# Motor.net
KiCad netlist of a schematic drawn in Altium Designer
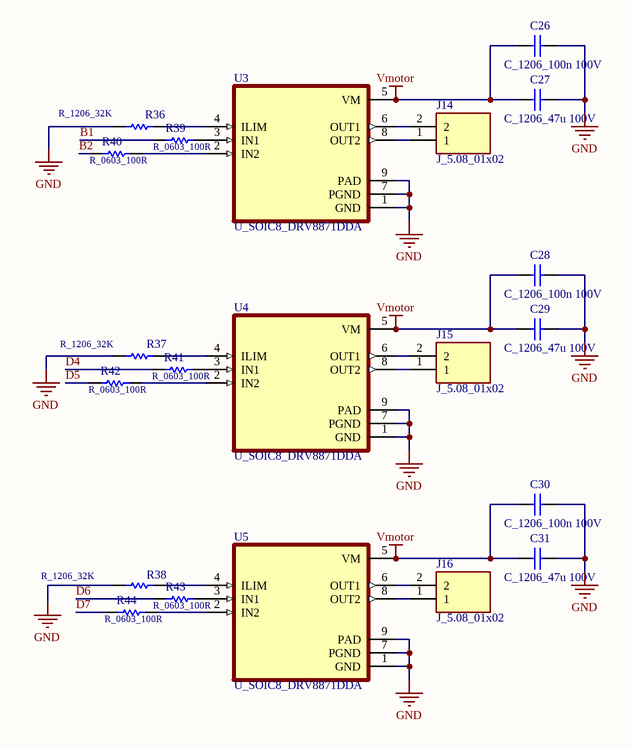
[diagram p0: Motor.SchDoc]

(export (version "E")
  (design (tool "Eeschema 10.0.6"))
  (components
    (comp (ref "C26")
      (value "C_1206_100n 100V")
      (footprint "CAP 1206")
      (description "Capacitor")
      (fields (field (name "PUBLISHER") "Altium Limited"))
      (libsource (lib "HUE") (part "Cap"))
    )
    (comp (ref "C27")
      (value "C_1206_47u 100V")
      (footprint "CAP 1206")
      (description "Capacitor")
      (fields (field (name "PUBLISHER") "Altium Limited"))
      (libsource (lib "HUE") (part "Cap"))
    )
    (comp (ref "C28")
      (value "C_1206_100n 100V")
      (footprint "CAP 1206")
      (description "Capacitor")
      (fields (field (name "PUBLISHER") "Altium Limited"))
      (libsource (lib "HUE") (part "Cap"))
    )
    (comp (ref "C29")
      (value "C_1206_47u 100V")
      (footprint "CAP 1206")
      (description "Capacitor")
      (fields (field (name "PUBLISHER") "Altium Limited"))
      (libsource (lib "HUE") (part "Cap"))
    )
    (comp (ref "C30")
      (value "C_1206_100n 100V")
      (footprint "CAP 1206")
      (description "Capacitor")
      (fields (field (name "PUBLISHER") "Altium Limited"))
      (libsource (lib "HUE") (part "Cap"))
    )
    (comp (ref "C31")
      (value "C_1206_47u 100V")
      (footprint "CAP 1206")
      (description "Capacitor")
      (fields (field (name "PUBLISHER") "Altium Limited"))
      (libsource (lib "HUE") (part "Cap"))
    )
    (comp (ref "J14")
      (value "J_5.08_01x02")
      (footprint "2 Pin PCB STB 5.08")
      (fields (field (name "MF") "CUI Devices") (field (name "MP") "TBP02R1-381-02BE"))
      (libsource (lib "HUE") (part "2 Pin PCB Terminal Block"))
    )
    (comp (ref "J15")
      (value "J_5.08_01x02")
      (footprint "2 Pin PCB STB 5.08")
      (fields (field (name "MF") "CUI Devices") (field (name "MP") "TBP02R1-381-02BE"))
      (libsource (lib "HUE") (part "2 Pin PCB Terminal Block"))
    )
    (comp (ref "J16")
      (value "J_5.08_01x02")
      (footprint "2 Pin PCB STB 5.08")
      (fields (field (name "MF") "CUI Devices") (field (name "MP") "TBP02R1-381-02BE"))
      (libsource (lib "HUE") (part "2 Pin PCB Terminal Block"))
    )
    (comp (ref "R36")
      (value "R_1206_32K")
      (footprint "RES 1206")
      (description "Resistor")
      (fields (field (name "PUBLISHER") "Altium Limited"))
      (libsource (lib "HUE") (part "Res"))
    )
    (comp (ref "R37")
      (value "R_1206_32K")
      (footprint "RES 1206")
      (description "Resistor")
      (fields (field (name "PUBLISHER") "Altium Limited"))
      (libsource (lib "HUE") (part "Res"))
    )
    (comp (ref "R38")
      (value "R_1206_32K")
      (footprint "RES 1206")
      (description "Resistor")
      (fields (field (name "PUBLISHER") "Altium Limited"))
      (libsource (lib "HUE") (part "Res"))
    )
    (comp (ref "R39")
      (value "R_0603_100R")
      (footprint "RES 1206")
      (description "Resistor")
      (fields (field (name "PUBLISHER") "Altium Limited"))
      (libsource (lib "HUE") (part "Res"))
    )
    (comp (ref "R40")
      (value "R_0603_100R")
      (footprint "RES 1206")
      (description "Resistor")
      (fields (field (name "PUBLISHER") "Altium Limited"))
      (libsource (lib "HUE") (part "Res"))
    )
    (comp (ref "R41")
      (value "R_0603_100R")
      (footprint "RES 1206")
      (description "Resistor")
      (fields (field (name "PUBLISHER") "Altium Limited"))
      (libsource (lib "HUE") (part "Res"))
    )
    (comp (ref "R42")
      (value "R_0603_100R")
      (footprint "RES 1206")
      (description "Resistor")
      (fields (field (name "PUBLISHER") "Altium Limited"))
      (libsource (lib "HUE") (part "Res"))
    )
    (comp (ref "R43")
      (value "R_0603_100R")
      (footprint "RES 1206")
      (description "Resistor")
      (fields (field (name "PUBLISHER") "Altium Limited"))
      (libsource (lib "HUE") (part "Res"))
    )
    (comp (ref "R44")
      (value "R_0603_100R")
      (footprint "RES 1206")
      (description "Resistor")
      (fields (field (name "PUBLISHER") "Altium Limited"))
      (libsource (lib "HUE") (part "Res"))
    )
    (comp (ref "U3")
      (value "U_SOIC8_DRV8871DDA")
      (footprint "SOIC8")
      (description "45-V, 3.6-A H-bridge motor driver with integrated current sensing 8-SO PowerPAD -40 to 125")
      (fields (field (name "MP") "DRV8871DDA") (field (name "MF") "Texas Instruments"))
      (libsource (lib "HUE") (part "DRV8871DDA"))
    )
    (comp (ref "U4")
      (value "U_SOIC8_DRV8871DDA")
      (footprint "SOIC8")
      (description "45-V, 3.6-A H-bridge motor driver with integrated current sensing 8-SO PowerPAD -40 to 125")
      (fields (field (name "MP") "DRV8871DDA") (field (name "MF") "Texas Instruments"))
      (libsource (lib "HUE") (part "DRV8871DDA"))
    )
    (comp (ref "U5")
      (value "U_SOIC8_DRV8871DDA")
      (footprint "SOIC8")
      (description "45-V, 3.6-A H-bridge motor driver with integrated current sensing 8-SO PowerPAD -40 to 125")
      (fields (field (name "MP") "DRV8871DDA") (field (name "MF") "Texas Instruments"))
      (libsource (lib "HUE") (part "DRV8871DDA"))
    )
  )
  (nets
    (net (code "1") (name "/B1") (class "Default")
      (node (ref "R39") (pin "1") (pinfunction "1_1") (pintype "passive"))
    )
    (net (code "2") (name "/B2") (class "Default")
      (node (ref "R40") (pin "1") (pinfunction "1_1") (pintype "passive"))
    )
    (net (code "3") (name "/D4") (class "Default")
      (node (ref "R41") (pin "1") (pinfunction "1_1") (pintype "passive"))
    )
    (net (code "4") (name "/D5") (class "Default")
      (node (ref "R42") (pin "1") (pinfunction "1_1") (pintype "passive"))
    )
    (net (code "5") (name "/D6") (class "Default")
      (node (ref "R43") (pin "1") (pinfunction "1_1") (pintype "passive"))
    )
    (net (code "6") (name "/D7") (class "Default")
      (node (ref "R44") (pin "1") (pinfunction "1_1") (pintype "passive"))
    )
    (net (code "7") (name "GND") (class "Default")
      (node (ref "C26") (pin "2") (pinfunction "2_2") (pintype "passive"))
      (node (ref "C27") (pin "2") (pinfunction "2_2") (pintype "passive"))
      (node (ref "C28") (pin "2") (pinfunction "2_2") (pintype "passive"))
      (node (ref "C29") (pin "2") (pinfunction "2_2") (pintype "passive"))
      (node (ref "C30") (pin "2") (pinfunction "2_2") (pintype "passive"))
      (node (ref "C31") (pin "2") (pinfunction "2_2") (pintype "passive"))
      (node (ref "R36") (pin "1") (pinfunction "1_1") (pintype "passive"))
      (node (ref "R37") (pin "1") (pinfunction "1_1") (pintype "passive"))
      (node (ref "R38") (pin "1") (pinfunction "1_1") (pintype "passive"))
      (node (ref "U3") (pin "1") (pinfunction "GND_1") (pintype "power_in"))
      (node (ref "U3") (pin "7") (pinfunction "PGND_7") (pintype "power_in"))
      (node (ref "U3") (pin "9") (pinfunction "PAD_9") (pintype "power_in"))
      (node (ref "U4") (pin "1") (pinfunction "GND_1") (pintype "power_in"))
      (node (ref "U4") (pin "7") (pinfunction "PGND_7") (pintype "power_in"))
      (node (ref "U4") (pin "9") (pinfunction "PAD_9") (pintype "power_in"))
      (node (ref "U5") (pin "1") (pinfunction "GND_1") (pintype "power_in"))
      (node (ref "U5") (pin "7") (pinfunction "PGND_7") (pintype "power_in"))
      (node (ref "U5") (pin "9") (pinfunction "PAD_9") (pintype "power_in"))
    )
    (net (code "8") (name "Net-(U3-ILIM)") (class "Default")
      (node (ref "R36") (pin "2") (pinfunction "2_2") (pintype "passive"))
      (node (ref "U3") (pin "4") (pinfunction "ILIM_4") (pintype "input"))
    )
    (net (code "9") (name "Net-(U3-IN1)") (class "Default")
      (node (ref "R39") (pin "2") (pinfunction "2_2") (pintype "passive"))
      (node (ref "U3") (pin "3") (pinfunction "IN1_3") (pintype "input"))
    )
    (net (code "10") (name "Net-(U3-IN2)") (class "Default")
      (node (ref "R40") (pin "2") (pinfunction "2_2") (pintype "passive"))
      (node (ref "U3") (pin "2") (pinfunction "IN2_2") (pintype "input"))
    )
    (net (code "11") (name "Net-(U3-OUT1)") (class "Default")
      (node (ref "J14") (pin "2") (pinfunction "2_2") (pintype "passive"))
      (node (ref "U3") (pin "6") (pinfunction "OUT1_6") (pintype "output"))
    )
    (net (code "12") (name "Net-(U3-OUT2)") (class "Default")
      (node (ref "J14") (pin "1") (pinfunction "1_1") (pintype "passive"))
      (node (ref "U3") (pin "8") (pinfunction "OUT2_8") (pintype "output"))
    )
    (net (code "13") (name "Net-(U4-ILIM)") (class "Default")
      (node (ref "R37") (pin "2") (pinfunction "2_2") (pintype "passive"))
      (node (ref "U4") (pin "4") (pinfunction "ILIM_4") (pintype "input"))
    )
    (net (code "14") (name "Net-(U4-IN1)") (class "Default")
      (node (ref "R41") (pin "2") (pinfunction "2_2") (pintype "passive"))
      (node (ref "U4") (pin "3") (pinfunction "IN1_3") (pintype "input"))
    )
    (net (code "15") (name "Net-(U4-IN2)") (class "Default")
      (node (ref "R42") (pin "2") (pinfunction "2_2") (pintype "passive"))
      (node (ref "U4") (pin "2") (pinfunction "IN2_2") (pintype "input"))
    )
    (net (code "16") (name "Net-(U4-OUT1)") (class "Default")
      (node (ref "J15") (pin "2") (pinfunction "2_2") (pintype "passive"))
      (node (ref "U4") (pin "6") (pinfunction "OUT1_6") (pintype "output"))
    )
    (net (code "17") (name "Net-(U4-OUT2)") (class "Default")
      (node (ref "J15") (pin "1") (pinfunction "1_1") (pintype "passive"))
      (node (ref "U4") (pin "8") (pinfunction "OUT2_8") (pintype "output"))
    )
    (net (code "18") (name "Net-(U5-ILIM)") (class "Default")
      (node (ref "R38") (pin "2") (pinfunction "2_2") (pintype "passive"))
      (node (ref "U5") (pin "4") (pinfunction "ILIM_4") (pintype "input"))
    )
    (net (code "19") (name "Net-(U5-IN1)") (class "Default")
      (node (ref "R43") (pin "2") (pinfunction "2_2") (pintype "passive"))
      (node (ref "U5") (pin "3") (pinfunction "IN1_3") (pintype "input"))
    )
    (net (code "20") (name "Net-(U5-IN2)") (class "Default")
      (node (ref "R44") (pin "2") (pinfunction "2_2") (pintype "passive"))
      (node (ref "U5") (pin "2") (pinfunction "IN2_2") (pintype "input"))
    )
    (net (code "21") (name "Net-(U5-OUT1)") (class "Default")
      (node (ref "J16") (pin "2") (pinfunction "2_2") (pintype "passive"))
      (node (ref "U5") (pin "6") (pinfunction "OUT1_6") (pintype "output"))
    )
    (net (code "22") (name "Net-(U5-OUT2)") (class "Default")
      (node (ref "J16") (pin "1") (pinfunction "1_1") (pintype "passive"))
      (node (ref "U5") (pin "8") (pinfunction "OUT2_8") (pintype "output"))
    )
    (net (code "23") (name "Vmotor") (class "Default")
      (node (ref "C26") (pin "1") (pinfunction "1_1") (pintype "passive"))
      (node (ref "C27") (pin "1") (pinfunction "1_1") (pintype "passive"))
      (node (ref "C28") (pin "1") (pinfunction "1_1") (pintype "passive"))
      (node (ref "C29") (pin "1") (pinfunction "1_1") (pintype "passive"))
      (node (ref "C30") (pin "1") (pinfunction "1_1") (pintype "passive"))
      (node (ref "C31") (pin "1") (pinfunction "1_1") (pintype "passive"))
      (node (ref "U3") (pin "5") (pinfunction "VM_5") (pintype "power_in"))
      (node (ref "U4") (pin "5") (pinfunction "VM_5") (pintype "power_in"))
      (node (ref "U5") (pin "5") (pinfunction "VM_5") (pintype "power_in"))
    )
  )
)
